# Master.net
KiCad netlist of a schematic drawn in Altium Designer
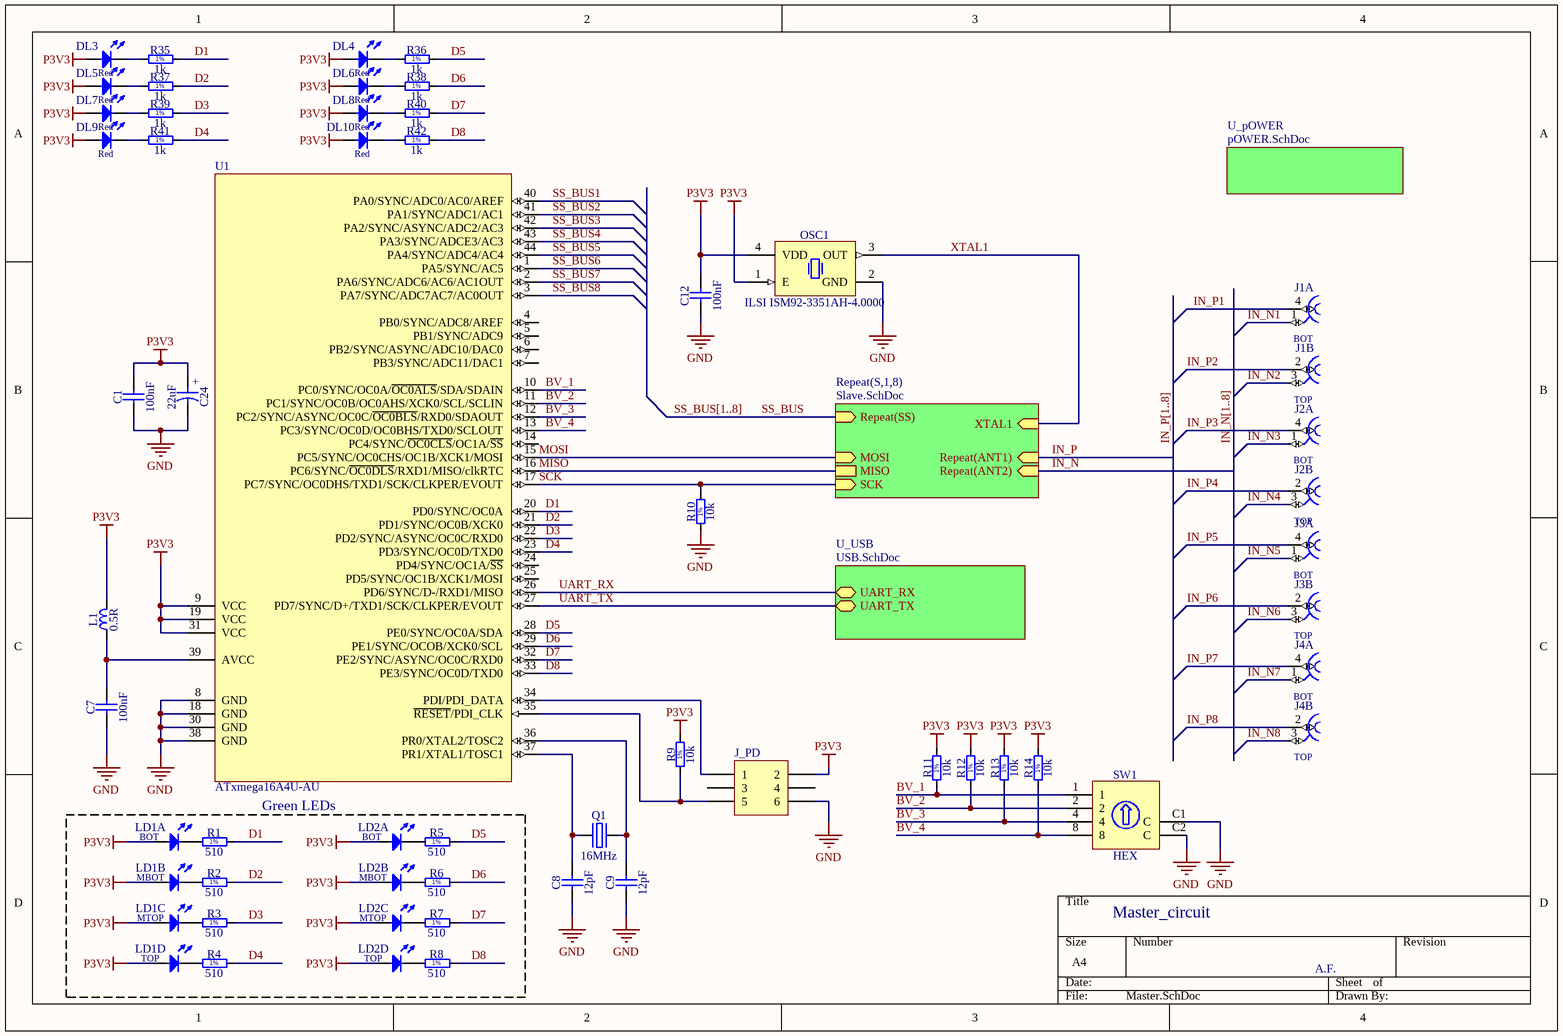
[diagram p0: Master.SchDoc]

(export (version "E")
  (design (tool "Eeschema 10.0.6"))
  (components
    (comp (ref "C1")
      (value "100nF")
      (footprint "CAPC1608X87N")
      (description "Non-polarised capacitor")
      (fields
        (field (name "PART NUMBER") "CC0603_100NF_50V_10%_X5R")
        (field (name "VOLTAGE") "50V")
        (field (name "AUTHOR") "CERN DEM MR")
      )
      (libsource (lib "Capacitors") (part "Capacitor - non polarized"))
    )
    (comp (ref "C7")
      (value "100nF")
      (footprint "CAPC1608X87N")
      (description "Non-polarised capacitor")
      (fields
        (field (name "PART NUMBER") "CC0603_100NF_50V_10%_X5R")
        (field (name "VOLTAGE") "50V")
        (field (name "AUTHOR") "CERN DEM MR")
      )
      (libsource (lib "Capacitors") (part "Capacitor - non polarized"))
    )
    (comp (ref "C8")
      (value "12pF")
      (footprint "CAPC1608X87N")
      (description "Non-polarised capacitor")
      (fields
        (field (name "PART NUMBER") "CC0603_12PF_50V_5%_NP0")
        (field (name "VOLTAGE") "50V")
        (field (name "AUTHOR") "CERN DEM JLC")
      )
      (libsource (lib "Capacitors") (part "Capacitor - non polarized"))
    )
    (comp (ref "C9")
      (value "12pF")
      (footprint "CAPC1608X87N")
      (description "Non-polarised capacitor")
      (fields
        (field (name "PART NUMBER") "CC0603_12PF_50V_5%_NP0")
        (field (name "VOLTAGE") "50V")
        (field (name "AUTHOR") "CERN DEM JLC")
      )
      (libsource (lib "Capacitors") (part "Capacitor - non polarized"))
    )
    (comp (ref "C12")
      (value "100nF")
      (footprint "CAPC1608X87N")
      (description "Non-polarised capacitor")
      (fields
        (field (name "PART NUMBER") "CC0603_100NF_50V_10%_X5R")
        (field (name "VOLTAGE") "50V")
        (field (name "AUTHOR") "CERN DEM MR")
      )
      (libsource (lib "Capacitors") (part "Capacitor - non polarized"))
    )
    (comp (ref "C24")
      (value "22uF")
      (footprint "CAPAE430X540N")
      (description "Polarised capacitor")
      (fields
        (field (name "PART NUMBER") "CAE430-540_22UF_10V_20%")
        (field (name "VOLTAGE") "10V")
        (field (name "AUTHOR") "CERN DEM JLC")
      )
      (libsource (lib "Capacitors") (part "Capacitor - polarized"))
    )
    (comp (ref "DL3")
      (value "Red")
      (footprint "LED_OSRAM_LSR976")
      (description "LED Red 1C 2A")
      (fields
        (field (name "PART NUMBER") "LED_OSRAM_LSR976")
        (field (name "MANUFACTURER") "OSRAM")
        (field (name "AUTHOR") "CERN DEM JLC")
      )
      (libsource (lib "ICs And Semiconductors") (part "LED Red 1C 2A"))
    )
    (comp (ref "DL4")
      (value "Red")
      (footprint "LED_OSRAM_LSR976")
      (description "LED Red 1C 2A")
      (fields
        (field (name "PART NUMBER") "LED_OSRAM_LSR976")
        (field (name "MANUFACTURER") "OSRAM")
        (field (name "AUTHOR") "CERN DEM JLC")
      )
      (libsource (lib "ICs And Semiconductors") (part "LED Red 1C 2A"))
    )
    (comp (ref "DL5")
      (value "Red")
      (footprint "LED_OSRAM_LSR976")
      (description "LED Red 1C 2A")
      (fields
        (field (name "PART NUMBER") "LED_OSRAM_LSR976")
        (field (name "MANUFACTURER") "OSRAM")
        (field (name "AUTHOR") "CERN DEM JLC")
      )
      (libsource (lib "ICs And Semiconductors") (part "LED Red 1C 2A"))
    )
    (comp (ref "DL6")
      (value "Red")
      (footprint "LED_OSRAM_LSR976")
      (description "LED Red 1C 2A")
      (fields
        (field (name "PART NUMBER") "LED_OSRAM_LSR976")
        (field (name "MANUFACTURER") "OSRAM")
        (field (name "AUTHOR") "CERN DEM JLC")
      )
      (libsource (lib "ICs And Semiconductors") (part "LED Red 1C 2A"))
    )
    (comp (ref "DL7")
      (value "Red")
      (footprint "LED_OSRAM_LSR976")
      (description "LED Red 1C 2A")
      (fields
        (field (name "PART NUMBER") "LED_OSRAM_LSR976")
        (field (name "MANUFACTURER") "OSRAM")
        (field (name "AUTHOR") "CERN DEM JLC")
      )
      (libsource (lib "ICs And Semiconductors") (part "LED Red 1C 2A"))
    )
    (comp (ref "DL8")
      (value "Red")
      (footprint "LED_OSRAM_LSR976")
      (description "LED Red 1C 2A")
      (fields
        (field (name "PART NUMBER") "LED_OSRAM_LSR976")
        (field (name "MANUFACTURER") "OSRAM")
        (field (name "AUTHOR") "CERN DEM JLC")
      )
      (libsource (lib "ICs And Semiconductors") (part "LED Red 1C 2A"))
    )
    (comp (ref "DL9")
      (value "Red")
      (footprint "LED_OSRAM_LSR976")
      (description "LED Red 1C 2A")
      (fields
        (field (name "PART NUMBER") "LED_OSRAM_LSR976")
        (field (name "MANUFACTURER") "OSRAM")
        (field (name "AUTHOR") "CERN DEM JLC")
      )
      (libsource (lib "ICs And Semiconductors") (part "LED Red 1C 2A"))
    )
    (comp (ref "DL10")
      (value "Red")
      (footprint "LED_OSRAM_LSR976")
      (description "LED Red 1C 2A")
      (fields
        (field (name "PART NUMBER") "LED_OSRAM_LSR976")
        (field (name "MANUFACTURER") "OSRAM")
        (field (name "AUTHOR") "CERN DEM JLC")
      )
      (libsource (lib "ICs And Semiconductors") (part "LED Red 1C 2A"))
    )
    (comp (ref "J1")
      (value "BNC")
      (footprint "RENHOTEC_RHT-610-0049")
      (description "Dual Right Angle 50 Ohm BNC Jack, White Valox Case")
      (fields
        (field (name "PART NUMBER") "RENHOTEC_RHT-610-0049")
        (field (name "MANUFACTURER") "RENHOTEC")
        (field (name "AUTHOR") "GK")
      )
      (libsource (lib "LIBRARY_SCH") (part "CON_BNC_DUAL"))
    )
    (comp (ref "J2")
      (value "Family")
      (footprint "RENHOTEC_RHT-610-0049")
      (description "Dual Right Angle 50 Ohm BNC Jack, White Valox Case")
      (fields
        (field (name "PART NUMBER") "RENHOTEC_RHT-610-0049")
        (field (name "MANUFACTURER") "RENHOTEC")
        (field (name "AUTHOR") "GK")
      )
      (libsource (lib "LIBRARY_SCH") (part "CON_BNC_DUAL"))
    )
    (comp (ref "J3")
      (value "Family")
      (footprint "RENHOTEC_RHT-610-0049")
      (description "Dual Right Angle 50 Ohm BNC Jack, White Valox Case")
      (fields
        (field (name "PART NUMBER") "RENHOTEC_RHT-610-0049")
        (field (name "MANUFACTURER") "RENHOTEC")
        (field (name "AUTHOR") "GK")
      )
      (libsource (lib "LIBRARY_SCH") (part "CON_BNC_DUAL"))
    )
    (comp (ref "J4")
      (value "Family")
      (footprint "RENHOTEC_RHT-610-0049")
      (description "Dual Right Angle 50 Ohm BNC Jack, White Valox Case")
      (fields
        (field (name "PART NUMBER") "RENHOTEC_RHT-610-0049")
        (field (name "MANUFACTURER") "RENHOTEC")
        (field (name "AUTHOR") "GK")
      )
      (libsource (lib "LIBRARY_SCH") (part "CON_BNC_DUAL"))
    )
    (comp (ref "J_PD")
      (value "~")
      (footprint "HDR2X3")
      (description "Header, 3-Pin, Dual row")
      (fields (field (name "PUBLISHER") "Altium Limited"))
      (libsource (lib "Miscellaneous Connectors") (part "Header 3X2"))
    )
    (comp (ref "L1")
      (value "0.5R")
      (footprint "Miscellaneous Devices:1608[0603]")
      (description "Ferrite Bead")
      (fields
        (field (name "POWER") "0.5A")
        (field (name "MANUFACTURER") "MURATA")
        (field (name "AUTHOR") "CERN DEM BC")
      )
      (libsource (lib "altium-import") (part "root_1_Inductor_"))
    )
    (comp (ref "LD1")
      (value "Green")
      (footprint "LED_BIVAR_H485CGDL")
      (description "LED x4 Green 1C2A-BOT_3C4A_5C6A_7C8A-TOP")
      (fields
        (field (name "PART NUMBER") "LED_BIVAR_H485CGDL")
        (field (name "MANUFACTURER") "BIVAR")
        (field (name "AUTHOR") "CERN DEM JLC")
      )
      (libsource (lib "RFID_system") (part "LED x4 Green 1C2A-BOT_3C4A_5C6A_7C8A-TOP"))
    )
    (comp (ref "LD2")
      (value "Green")
      (footprint "LED_BIVAR_H485CGDL")
      (description "LED x4 Green 1C2A-BOT_3C4A_5C6A_7C8A-TOP")
      (fields
        (field (name "PART NUMBER") "LED_BIVAR_H485CGDL")
        (field (name "MANUFACTURER") "BIVAR")
        (field (name "AUTHOR") "CERN DEM JLC")
      )
      (libsource (lib "RFID_system") (part "LED x4 Green 1C2A-BOT_3C4A_5C6A_7C8A-TOP"))
    )
    (comp (ref "OSC1")
      (value "ILSI ISM92-3351AH-4.0000")
      (footprint "OSCSC250P320X500X130-4N")
      (description "Oscillator 4 pins 3.3V 4MHz")
      (libsource (lib "Crystals & Oscillators") (part "Oscillator 1E 2GND 3OUT 4VDD"))
    )
    (comp (ref "Q1")
      (value "16MHz")
      (footprint "XTAL1160X490X430")
      (description "Quartz Crystal")
      (fields
        (field (name "PART NUMBER") "XTAL_16MHZ_IQD_LFXTAL003237")
        (field (name "MANUFACTURER") "IQD FREQUENCY PRODUCTS")
        (field (name "AUTHOR") "CERN DEM MR")
      )
      (libsource (lib "ICs And Semiconductors") (part "Quartz Crystal"))
    )
    (comp (ref "R1")
      (value "510")
      (footprint "RESC1608X55N")
      (description "Resistor - 1%")
      (fields
        (field (name "PART NUMBER") "R0603_510R_1%_0.1W_100PPM")
        (field (name "POWER") "0.1W")
        (field (name "AUTHOR") "CERN DEM JLC")
      )
      (libsource (lib "Resistors") (part "Resistor - 1%"))
    )
    (comp (ref "R2")
      (value "510")
      (footprint "RESC1608X55N")
      (description "Resistor - 1%")
      (fields
        (field (name "PART NUMBER") "R0603_510R_1%_0.1W_100PPM")
        (field (name "POWER") "0.1W")
        (field (name "AUTHOR") "CERN DEM JLC")
      )
      (libsource (lib "Resistors") (part "Resistor - 1%"))
    )
    (comp (ref "R3")
      (value "510")
      (footprint "RESC1608X55N")
      (description "Resistor - 1%")
      (fields
        (field (name "PART NUMBER") "R0603_510R_1%_0.1W_100PPM")
        (field (name "POWER") "0.1W")
        (field (name "AUTHOR") "CERN DEM JLC")
      )
      (libsource (lib "Resistors") (part "Resistor - 1%"))
    )
    (comp (ref "R4")
      (value "510")
      (footprint "RESC1608X55N")
      (description "Resistor - 1%")
      (fields
        (field (name "PART NUMBER") "R0603_510R_1%_0.1W_100PPM")
        (field (name "POWER") "0.1W")
        (field (name "AUTHOR") "CERN DEM JLC")
      )
      (libsource (lib "Resistors") (part "Resistor - 1%"))
    )
    (comp (ref "R5")
      (value "510")
      (footprint "RESC1608X55N")
      (description "Resistor - 1%")
      (fields
        (field (name "PART NUMBER") "R0603_510R_1%_0.1W_100PPM")
        (field (name "POWER") "0.1W")
        (field (name "AUTHOR") "CERN DEM JLC")
      )
      (libsource (lib "Resistors") (part "Resistor - 1%"))
    )
    (comp (ref "R6")
      (value "510")
      (footprint "RESC1608X55N")
      (description "Resistor - 1%")
      (fields
        (field (name "PART NUMBER") "R0603_510R_1%_0.1W_100PPM")
        (field (name "POWER") "0.1W")
        (field (name "AUTHOR") "CERN DEM JLC")
      )
      (libsource (lib "Resistors") (part "Resistor - 1%"))
    )
    (comp (ref "R7")
      (value "510")
      (footprint "RESC1608X55N")
      (description "Resistor - 1%")
      (fields
        (field (name "PART NUMBER") "R0603_510R_1%_0.1W_100PPM")
        (field (name "POWER") "0.1W")
        (field (name "AUTHOR") "CERN DEM JLC")
      )
      (libsource (lib "Resistors") (part "Resistor - 1%"))
    )
    (comp (ref "R8")
      (value "510")
      (footprint "RESC1608X55N")
      (description "Resistor - 1%")
      (fields
        (field (name "PART NUMBER") "R0603_510R_1%_0.1W_100PPM")
        (field (name "POWER") "0.1W")
        (field (name "AUTHOR") "CERN DEM JLC")
      )
      (libsource (lib "Resistors") (part "Resistor - 1%"))
    )
    (comp (ref "R9")
      (value "10k")
      (footprint "RESC1608X55N")
      (description "Resistor - 1%")
      (fields
        (field (name "PART NUMBER") "R0603_10K_1%_0.1W_100PPM")
        (field (name "POWER") "0.1W")
        (field (name "AUTHOR") "CERN DEM JLC")
      )
      (libsource (lib "Resistors") (part "Resistor - 1%"))
    )
    (comp (ref "R10")
      (value "10k")
      (footprint "RESC1608X55N")
      (description "Resistor - 1%")
      (fields
        (field (name "PART NUMBER") "R0603_10K_1%_0.1W_100PPM")
        (field (name "POWER") "0.1W")
        (field (name "AUTHOR") "CERN DEM JLC")
      )
      (libsource (lib "Resistors") (part "Resistor - 1%"))
    )
    (comp (ref "R11")
      (value "10k")
      (footprint "RESC1608X55N")
      (description "Resistor - 1%")
      (fields
        (field (name "PART NUMBER") "R0603_10K_1%_0.1W_100PPM")
        (field (name "POWER") "0.1W")
        (field (name "AUTHOR") "CERN DEM JLC")
      )
      (libsource (lib "Resistors") (part "Resistor - 1%"))
    )
    (comp (ref "R12")
      (value "10k")
      (footprint "RESC1608X55N")
      (description "Resistor - 1%")
      (fields
        (field (name "PART NUMBER") "R0603_10K_1%_0.1W_100PPM")
        (field (name "POWER") "0.1W")
        (field (name "AUTHOR") "CERN DEM JLC")
      )
      (libsource (lib "Resistors") (part "Resistor - 1%"))
    )
    (comp (ref "R13")
      (value "10k")
      (footprint "RESC1608X55N")
      (description "Resistor - 1%")
      (fields
        (field (name "PART NUMBER") "R0603_10K_1%_0.1W_100PPM")
        (field (name "POWER") "0.1W")
        (field (name "AUTHOR") "CERN DEM JLC")
      )
      (libsource (lib "Resistors") (part "Resistor - 1%"))
    )
    (comp (ref "R14")
      (value "10k")
      (footprint "RESC1608X55N")
      (description "Resistor - 1%")
      (fields
        (field (name "PART NUMBER") "R0603_10K_1%_0.1W_100PPM")
        (field (name "POWER") "0.1W")
        (field (name "AUTHOR") "CERN DEM JLC")
      )
      (libsource (lib "Resistors") (part "Resistor - 1%"))
    )
    (comp (ref "R35")
      (value "1k")
      (footprint "RESC1608X50N")
      (description "Resistor - 1%")
      (fields
        (field (name "PART NUMBER") "R0805_1K_1%_0.33W_100PPM_VISHAY_CRCW-HP")
        (field (name "POWER") "0.33W")
        (field (name "AUTHOR") "CERN DEM JLC")
      )
      (libsource (lib "Resistors") (part "Resistor - 1%"))
    )
    (comp (ref "R36")
      (value "1k")
      (footprint "RESC1608X50N")
      (description "Resistor - 1%")
      (fields
        (field (name "PART NUMBER") "R0805_1K_1%_0.33W_100PPM_VISHAY_CRCW-HP")
        (field (name "POWER") "0.33W")
        (field (name "AUTHOR") "CERN DEM JLC")
      )
      (libsource (lib "Resistors") (part "Resistor - 1%"))
    )
    (comp (ref "R37")
      (value "1k")
      (footprint "RESC1608X50N")
      (description "Resistor - 1%")
      (fields
        (field (name "PART NUMBER") "R0805_1K_1%_0.33W_100PPM_VISHAY_CRCW-HP")
        (field (name "POWER") "0.33W")
        (field (name "AUTHOR") "CERN DEM JLC")
      )
      (libsource (lib "Resistors") (part "Resistor - 1%"))
    )
    (comp (ref "R38")
      (value "1k")
      (footprint "RESC1608X50N")
      (description "Resistor - 1%")
      (fields
        (field (name "PART NUMBER") "R0805_1K_1%_0.33W_100PPM_VISHAY_CRCW-HP")
        (field (name "POWER") "0.33W")
        (field (name "AUTHOR") "CERN DEM JLC")
      )
      (libsource (lib "Resistors") (part "Resistor - 1%"))
    )
    (comp (ref "R39")
      (value "1k")
      (footprint "RESC1608X50N")
      (description "Resistor - 1%")
      (fields
        (field (name "PART NUMBER") "R0805_1K_1%_0.33W_100PPM_VISHAY_CRCW-HP")
        (field (name "POWER") "0.33W")
        (field (name "AUTHOR") "CERN DEM JLC")
      )
      (libsource (lib "Resistors") (part "Resistor - 1%"))
    )
    (comp (ref "R40")
      (value "1k")
      (footprint "RESC1608X50N")
      (description "Resistor - 1%")
      (fields
        (field (name "PART NUMBER") "R0805_1K_1%_0.33W_100PPM_VISHAY_CRCW-HP")
        (field (name "POWER") "0.33W")
        (field (name "AUTHOR") "CERN DEM JLC")
      )
      (libsource (lib "Resistors") (part "Resistor - 1%"))
    )
    (comp (ref "R41")
      (value "1k")
      (footprint "RESC1608X50N")
      (description "Resistor - 1%")
      (fields
        (field (name "PART NUMBER") "R0805_1K_1%_0.33W_100PPM_VISHAY_CRCW-HP")
        (field (name "POWER") "0.33W")
        (field (name "AUTHOR") "CERN DEM JLC")
      )
      (libsource (lib "Resistors") (part "Resistor - 1%"))
    )
    (comp (ref "R42")
      (value "1k")
      (footprint "RESC1608X50N")
      (description "Resistor - 1%")
      (fields
        (field (name "PART NUMBER") "R0805_1K_1%_0.33W_100PPM_VISHAY_CRCW-HP")
        (field (name "POWER") "0.33W")
        (field (name "AUTHOR") "CERN DEM JLC")
      )
      (libsource (lib "Resistors") (part "Resistor - 1%"))
    )
    (comp (ref "SW1")
      (value "HEX")
      (footprint "SW_OMRON_A6RV-162RF")
      (description "Rotary Code Switch 1 2 4 8 C1 C2")
      (fields
        (field (name "PART NUMBER") "SW_OMRON_A6RV-162RF or ERD716RR")
        (field (name "MANUFACTURER") "OMRON")
        (field (name "AUTHOR") "CERN DEM JLC")
      )
      (libsource (lib "Eletro-mechanical") (part "SW Rotary 1 2 4 8 C1 C2"))
    )
    (comp (ref "U1")
      (value "ATxmega16A4U-AU")
      (footprint "44A_N")
      (fields (field (name "PUBLISHER") "Altium Limited"))
      (libsource (lib "RFID_system_atxmegau") (part "ATxmega16A4-AU"))
    )
  )
  (nets
    (net (code "2") (name "/BV_1") (class "Default")
      (node (ref "R11") (pin "1") (pinfunction "1_1") (pintype "passive"))
      (node (ref "SW1") (pin "1") (pinfunction "1_1") (pintype "passive"))
      (node (ref "U1") (pin "10") (pinfunction "PC0/SYNC/OC0A/~{OC0ALS}/SDA/SDAIN_10") (pintype "bidirectional"))
    )
    (net (code "3") (name "/BV_2") (class "Default")
      (node (ref "R12") (pin "1") (pinfunction "1_1") (pintype "passive"))
      (node (ref "SW1") (pin "2") (pinfunction "2_2") (pintype "passive"))
      (node (ref "U1") (pin "11") (pinfunction "PC1/SYNC/OC0B/OC0AHS/XCK0/SCL/SCLIN_11") (pintype "bidirectional"))
    )
    (net (code "4") (name "/BV_3") (class "Default")
      (node (ref "R13") (pin "1") (pinfunction "1_1") (pintype "passive"))
      (node (ref "SW1") (pin "4") (pinfunction "4_4") (pintype "passive"))
      (node (ref "U1") (pin "12") (pinfunction "PC2/SYNC/ASYNC/OC0C/~{OC0BLS}/RXD0/SDAOUT_12") (pintype "bidirectional"))
    )
    (net (code "5") (name "/BV_4") (class "Default")
      (node (ref "R14") (pin "1") (pinfunction "1_1") (pintype "passive"))
      (node (ref "SW1") (pin "8") (pinfunction "8_8") (pintype "passive"))
      (node (ref "U1") (pin "13") (pinfunction "PC3/SYNC/OC0D/OC0BHS/TXD0/SCLOUT_13") (pintype "bidirectional"))
    )
    (net (code "6") (name "/D1") (class "Default")
      (node (ref "R1") (pin "2") (pinfunction "2_2") (pintype "passive"))
      (node (ref "R35") (pin "1") (pinfunction "1_1") (pintype "passive"))
      (node (ref "U1") (pin "20") (pinfunction "PD0/SYNC/OC0A_20") (pintype "bidirectional"))
    )
    (net (code "7") (name "/D2") (class "Default")
      (node (ref "R2") (pin "2") (pinfunction "2_2") (pintype "passive"))
      (node (ref "R37") (pin "1") (pinfunction "1_1") (pintype "passive"))
      (node (ref "U1") (pin "21") (pinfunction "PD1/SYNC/OC0B/XCK0_21") (pintype "bidirectional"))
    )
    (net (code "8") (name "/D3") (class "Default")
      (node (ref "R3") (pin "2") (pinfunction "2_2") (pintype "passive"))
      (node (ref "R39") (pin "1") (pinfunction "1_1") (pintype "passive"))
      (node (ref "U1") (pin "22") (pinfunction "PD2/SYNC/ASYNC/OC0C/RXD0_22") (pintype "bidirectional"))
    )
    (net (code "9") (name "/D4") (class "Default")
      (node (ref "R4") (pin "2") (pinfunction "2_2") (pintype "passive"))
      (node (ref "R41") (pin "1") (pinfunction "1_1") (pintype "passive"))
      (node (ref "U1") (pin "23") (pinfunction "PD3/SYNC/OC0D/TXD0_23") (pintype "bidirectional"))
    )
    (net (code "10") (name "/D5") (class "Default")
      (node (ref "R36") (pin "1") (pinfunction "1_1") (pintype "passive"))
      (node (ref "R5") (pin "2") (pinfunction "2_2") (pintype "passive"))
      (node (ref "U1") (pin "28") (pinfunction "PE0/SYNC/OC0A/SDA_28") (pintype "bidirectional"))
    )
    (net (code "11") (name "/D6") (class "Default")
      (node (ref "R38") (pin "1") (pinfunction "1_1") (pintype "passive"))
      (node (ref "R6") (pin "2") (pinfunction "2_2") (pintype "passive"))
      (node (ref "U1") (pin "29") (pinfunction "PE1/SYNC/OCOB/XCK0/SCL_29") (pintype "bidirectional"))
    )
    (net (code "12") (name "/D7") (class "Default")
      (node (ref "R40") (pin "1") (pinfunction "1_1") (pintype "passive"))
      (node (ref "R7") (pin "2") (pinfunction "2_2") (pintype "passive"))
      (node (ref "U1") (pin "32") (pinfunction "PE2/SYNC/ASYNC/OC0C/RXD0_32") (pintype "bidirectional"))
    )
    (net (code "13") (name "/D8") (class "Default")
      (node (ref "R42") (pin "1") (pinfunction "1_1") (pintype "passive"))
      (node (ref "R8") (pin "2") (pinfunction "2_2") (pintype "passive"))
      (node (ref "U1") (pin "33") (pinfunction "PE3/SYNC/OC0D/TXD0_33") (pintype "bidirectional"))
    )
    (net (code "15") (name "/IN_N1") (class "Default")
      (node (ref "J1") (pin "1") (pinfunction "1_1") (pintype "bidirectional"))
    )
    (net (code "16") (name "/IN_N2") (class "Default")
      (node (ref "J1") (pin "3") (pinfunction "3_3") (pintype "bidirectional"))
    )
    (net (code "17") (name "/IN_N3") (class "Default")
      (node (ref "J2") (pin "1") (pinfunction "1_1") (pintype "bidirectional"))
    )
    (net (code "18") (name "/IN_N4") (class "Default")
      (node (ref "J2") (pin "3") (pinfunction "3_3") (pintype "bidirectional"))
    )
    (net (code "19") (name "/IN_N5") (class "Default")
      (node (ref "J3") (pin "1") (pinfunction "1_1") (pintype "bidirectional"))
    )
    (net (code "20") (name "/IN_N6") (class "Default")
      (node (ref "J3") (pin "3") (pinfunction "3_3") (pintype "bidirectional"))
    )
    (net (code "21") (name "/IN_N7") (class "Default")
      (node (ref "J4") (pin "1") (pinfunction "1_1") (pintype "bidirectional"))
    )
    (net (code "22") (name "/IN_N8") (class "Default")
      (node (ref "J4") (pin "3") (pinfunction "3_3") (pintype "bidirectional"))
    )
    (net (code "25") (name "/IN_P1") (class "Default")
      (node (ref "J1") (pin "4") (pinfunction "4_4") (pintype "bidirectional"))
    )
    (net (code "26") (name "/IN_P2") (class "Default")
      (node (ref "J1") (pin "2") (pinfunction "2_2") (pintype "bidirectional"))
    )
    (net (code "27") (name "/IN_P3") (class "Default")
      (node (ref "J2") (pin "4") (pinfunction "4_4") (pintype "bidirectional"))
    )
    (net (code "28") (name "/IN_P4") (class "Default")
      (node (ref "J2") (pin "2") (pinfunction "2_2") (pintype "bidirectional"))
    )
    (net (code "29") (name "/IN_P5") (class "Default")
      (node (ref "J3") (pin "4") (pinfunction "4_4") (pintype "bidirectional"))
    )
    (net (code "30") (name "/IN_P6") (class "Default")
      (node (ref "J3") (pin "2") (pinfunction "2_2") (pintype "bidirectional"))
    )
    (net (code "31") (name "/IN_P7") (class "Default")
      (node (ref "J4") (pin "4") (pinfunction "4_4") (pintype "bidirectional"))
    )
    (net (code "32") (name "/IN_P8") (class "Default")
      (node (ref "J4") (pin "2") (pinfunction "2_2") (pintype "bidirectional"))
    )
    (net (code "34") (name "/MISO") (class "Default")
      (node (ref "U1") (pin "16") (pinfunction "PC6/SYNC/~{OC0DLS}/RXD1/MISO/clkRTC_16") (pintype "bidirectional"))
    )
    (net (code "35") (name "/MOSI") (class "Default")
      (node (ref "U1") (pin "15") (pinfunction "PC5/SYNC/OC0CHS/OC1B/XCK1/MOSI_15") (pintype "bidirectional"))
    )
    (net (code "36") (name "/SCK") (class "Default")
      (node (ref "R10") (pin "2") (pinfunction "2_2") (pintype "passive"))
      (node (ref "U1") (pin "17") (pinfunction "PC7/SYNC/OC0DHS/TXD1/SCK/CLKPER/EVOUT_17") (pintype "bidirectional"))
    )
    (net (code "38") (name "/SS_BUS1") (class "Default")
      (node (ref "U1") (pin "40") (pinfunction "PA0/SYNC/ADC0/AC0/AREF_40") (pintype "bidirectional"))
    )
    (net (code "39") (name "/SS_BUS2") (class "Default")
      (node (ref "U1") (pin "41") (pinfunction "PA1/SYNC/ADC1/AC1_41") (pintype "bidirectional"))
    )
    (net (code "40") (name "/SS_BUS3") (class "Default")
      (node (ref "U1") (pin "42") (pinfunction "PA2/SYNC/ASYNC/ADC2/AC3_42") (pintype "bidirectional"))
    )
    (net (code "41") (name "/SS_BUS4") (class "Default")
      (node (ref "U1") (pin "43") (pinfunction "PA3/SYNC/ADCE3/AC3_43") (pintype "bidirectional"))
    )
    (net (code "42") (name "/SS_BUS5") (class "Default")
      (node (ref "U1") (pin "44") (pinfunction "PA4/SYNC/ADC4/AC4_44") (pintype "bidirectional"))
    )
    (net (code "43") (name "/SS_BUS6") (class "Default")
      (node (ref "U1") (pin "1") (pinfunction "PA5/SYNC/AC5_1") (pintype "bidirectional"))
    )
    (net (code "44") (name "/SS_BUS7") (class "Default")
      (node (ref "U1") (pin "2") (pinfunction "PA6/SYNC/ADC6/AC6/AC1OUT_2") (pintype "bidirectional"))
    )
    (net (code "45") (name "/SS_BUS8") (class "Default")
      (node (ref "U1") (pin "3") (pinfunction "PA7/SYNC/ADC7AC7/AC0OUT_3") (pintype "bidirectional"))
    )
    (net (code "47") (name "/UART_RX") (class "Default")
      (node (ref "U1") (pin "26") (pinfunction "PD6/SYNC/D-/RXD1/MISO_26") (pintype "bidirectional"))
    )
    (net (code "48") (name "/UART_TX") (class "Default")
      (node (ref "U1") (pin "27") (pinfunction "PD7/SYNC/D+/TXD1/SCK/CLKPER/EVOUT_27") (pintype "bidirectional"))
    )
    (net (code "49") (name "/XTAL1") (class "Default")
      (node (ref "OSC1") (pin "3") (pinfunction "OUT_3") (pintype "output"))
    )
    (net (code "50") (name "GND") (class "Default")
      (node (ref "C1") (pin "1") (pinfunction "1_1") (pintype "passive"))
      (node (ref "C12") (pin "1") (pinfunction "1_1") (pintype "passive"))
      (node (ref "C24") (pin "2") (pinfunction "2_2") (pintype "passive"))
      (node (ref "C7") (pin "1") (pinfunction "1_1") (pintype "passive"))
      (node (ref "C8") (pin "1") (pinfunction "1_1") (pintype "passive"))
      (node (ref "C9") (pin "1") (pinfunction "1_1") (pintype "passive"))
      (node (ref "J_PD") (pin "6") (pinfunction "6_6") (pintype "passive"))
      (node (ref "OSC1") (pin "2") (pinfunction "GND_2") (pintype "power_in"))
      (node (ref "R10") (pin "1") (pinfunction "1_1") (pintype "passive"))
      (node (ref "SW1") (pin "C1") (pinfunction "C_C1") (pintype "passive"))
      (node (ref "SW1") (pin "C2") (pinfunction "C_C2") (pintype "passive"))
      (node (ref "U1") (pin "18") (pinfunction "GND_18") (pintype "power_in"))
      (node (ref "U1") (pin "30") (pinfunction "GND_30") (pintype "power_in"))
      (node (ref "U1") (pin "38") (pinfunction "GND_38") (pintype "power_in"))
      (node (ref "U1") (pin "8") (pinfunction "GND_8") (pintype "power_in"))
    )
    (net (code "51") (name "Net-(DL3-C)") (class "Default")
      (node (ref "DL3") (pin "1") (pinfunction "C_1") (pintype "passive"))
      (node (ref "R35") (pin "2") (pinfunction "2_2") (pintype "passive"))
    )
    (net (code "52") (name "Net-(DL4-C)") (class "Default")
      (node (ref "DL4") (pin "1") (pinfunction "C_1") (pintype "passive"))
      (node (ref "R36") (pin "2") (pinfunction "2_2") (pintype "passive"))
    )
    (net (code "53") (name "Net-(DL5-C)") (class "Default")
      (node (ref "DL5") (pin "1") (pinfunction "C_1") (pintype "passive"))
      (node (ref "R37") (pin "2") (pinfunction "2_2") (pintype "passive"))
    )
    (net (code "54") (name "Net-(DL6-C)") (class "Default")
      (node (ref "DL6") (pin "1") (pinfunction "C_1") (pintype "passive"))
      (node (ref "R38") (pin "2") (pinfunction "2_2") (pintype "passive"))
    )
    (net (code "55") (name "Net-(DL7-C)") (class "Default")
      (node (ref "DL7") (pin "1") (pinfunction "C_1") (pintype "passive"))
      (node (ref "R39") (pin "2") (pinfunction "2_2") (pintype "passive"))
    )
    (net (code "56") (name "Net-(DL8-C)") (class "Default")
      (node (ref "DL8") (pin "1") (pinfunction "C_1") (pintype "passive"))
      (node (ref "R40") (pin "2") (pinfunction "2_2") (pintype "passive"))
    )
    (net (code "57") (name "Net-(DL9-C)") (class "Default")
      (node (ref "DL9") (pin "1") (pinfunction "C_1") (pintype "passive"))
      (node (ref "R41") (pin "2") (pinfunction "2_2") (pintype "passive"))
    )
    (net (code "58") (name "Net-(DL10-C)") (class "Default")
      (node (ref "DL10") (pin "1") (pinfunction "C_1") (pintype "passive"))
      (node (ref "R42") (pin "2") (pinfunction "2_2") (pintype "passive"))
    )
    (net (code "59") (name "Net-(LD1A-C)") (class "Default")
      (node (ref "LD1") (pin "1") (pinfunction "C_1") (pintype "passive"))
      (node (ref "R1") (pin "1") (pinfunction "1_1") (pintype "passive"))
    )
    (net (code "60") (name "Net-(LD1B-C)") (class "Default")
      (node (ref "LD1") (pin "3") (pinfunction "C_3") (pintype "passive"))
      (node (ref "R2") (pin "1") (pinfunction "1_1") (pintype "passive"))
    )
    (net (code "61") (name "Net-(LD1C-C)") (class "Default")
      (node (ref "LD1") (pin "5") (pinfunction "C_5") (pintype "passive"))
      (node (ref "R3") (pin "1") (pinfunction "1_1") (pintype "passive"))
    )
    (net (code "62") (name "Net-(LD1D-C)") (class "Default")
      (node (ref "LD1") (pin "7") (pinfunction "C_7") (pintype "passive"))
      (node (ref "R4") (pin "1") (pinfunction "1_1") (pintype "passive"))
    )
    (net (code "63") (name "Net-(LD2A-C)") (class "Default")
      (node (ref "LD2") (pin "1") (pinfunction "C_1") (pintype "passive"))
      (node (ref "R5") (pin "1") (pinfunction "1_1") (pintype "passive"))
    )
    (net (code "64") (name "Net-(LD2B-C)") (class "Default")
      (node (ref "LD2") (pin "3") (pinfunction "C_3") (pintype "passive"))
      (node (ref "R6") (pin "1") (pinfunction "1_1") (pintype "passive"))
    )
    (net (code "65") (name "Net-(LD2C-C)") (class "Default")
      (node (ref "LD2") (pin "5") (pinfunction "C_5") (pintype "passive"))
      (node (ref "R7") (pin "1") (pinfunction "1_1") (pintype "passive"))
    )
    (net (code "66") (name "Net-(LD2D-C)") (class "Default")
      (node (ref "LD2") (pin "7") (pinfunction "C_7") (pintype "passive"))
      (node (ref "R8") (pin "1") (pinfunction "1_1") (pintype "passive"))
    )
    (net (code "67") (name "Net-(Q1-OSC1)") (class "Default")
      (node (ref "C8") (pin "2") (pinfunction "2_2") (pintype "passive"))
      (node (ref "Q1") (pin "1") (pinfunction "OSC1_1") (pintype "passive"))
      (node (ref "U1") (pin "37") (pinfunction "PR1/XTAL1/TOSC1_37") (pintype "bidirectional"))
    )
    (net (code "68") (name "Net-(Q1-OSC2)") (class "Default")
      (node (ref "C9") (pin "2") (pinfunction "2_2") (pintype "passive"))
      (node (ref "Q1") (pin "2") (pinfunction "OSC2_2") (pintype "passive"))
      (node (ref "U1") (pin "36") (pinfunction "PR0/XTAL2/TOSC2_36") (pintype "bidirectional"))
    )
    (net (code "69") (name "Net-(U1-AVCC)") (class "Default")
      (node (ref "C7") (pin "2") (pinfunction "2_2") (pintype "passive"))
      (node (ref "L1") (pin "1") (pinfunction "1_1") (pintype "passive"))
      (node (ref "U1") (pin "39") (pinfunction "AVCC_39") (pintype "power_in"))
    )
    (net (code "70") (name "Net-(U1-PDI{slash}PDI_DATA)") (class "Default")
      (node (ref "J_PD") (pin "1") (pinfunction "1_1") (pintype "passive"))
      (node (ref "U1") (pin "34") (pinfunction "PDI/PDI_DATA_34") (pintype "bidirectional"))
    )
    (net (code "71") (name "Net-(U1-~{RESET}{slash}PDI_CLK)") (class "Default")
      (node (ref "J_PD") (pin "5") (pinfunction "5_5") (pintype "passive"))
      (node (ref "R9") (pin "1") (pinfunction "1_1") (pintype "passive"))
      (node (ref "U1") (pin "35") (pinfunction "~{RESET}/PDI_CLK_35") (pintype "input"))
    )
    (net (code "72") (name "P3V3") (class "Default")
      (node (ref "C1") (pin "2") (pinfunction "2_2") (pintype "passive"))
      (node (ref "C12") (pin "2") (pinfunction "2_2") (pintype "passive"))
      (node (ref "C24") (pin "1") (pinfunction "1_1") (pintype "passive"))
      (node (ref "DL10") (pin "2") (pinfunction "A_2") (pintype "passive"))
      (node (ref "DL3") (pin "2") (pinfunction "A_2") (pintype "passive"))
      (node (ref "DL4") (pin "2") (pinfunction "A_2") (pintype "passive"))
      (node (ref "DL5") (pin "2") (pinfunction "A_2") (pintype "passive"))
      (node (ref "DL6") (pin "2") (pinfunction "A_2") (pintype "passive"))
      (node (ref "DL7") (pin "2") (pinfunction "A_2") (pintype "passive"))
      (node (ref "DL8") (pin "2") (pinfunction "A_2") (pintype "passive"))
      (node (ref "DL9") (pin "2") (pinfunction "A_2") (pintype "passive"))
      (node (ref "J_PD") (pin "2") (pinfunction "2_2") (pintype "passive"))
      (node (ref "L1") (pin "2") (pinfunction "2_2") (pintype "passive"))
      (node (ref "LD1") (pin "2") (pinfunction "A_2") (pintype "passive"))
      (node (ref "LD1") (pin "4") (pinfunction "A_4") (pintype "passive"))
      (node (ref "LD1") (pin "6") (pinfunction "A_6") (pintype "passive"))
      (node (ref "LD1") (pin "8") (pinfunction "A_8") (pintype "passive"))
      (node (ref "LD2") (pin "2") (pinfunction "A_2") (pintype "passive"))
      (node (ref "LD2") (pin "4") (pinfunction "A_4") (pintype "passive"))
      (node (ref "LD2") (pin "6") (pinfunction "A_6") (pintype "passive"))
      (node (ref "LD2") (pin "8") (pinfunction "A_8") (pintype "passive"))
      (node (ref "OSC1") (pin "1") (pinfunction "E_1") (pintype "input"))
      (node (ref "OSC1") (pin "4") (pinfunction "VDD_4") (pintype "power_in"))
      (node (ref "R11") (pin "2") (pinfunction "2_2") (pintype "passive"))
      (node (ref "R12") (pin "2") (pinfunction "2_2") (pintype "passive"))
      (node (ref "R13") (pin "2") (pinfunction "2_2") (pintype "passive"))
      (node (ref "R14") (pin "2") (pinfunction "2_2") (pintype "passive"))
      (node (ref "R9") (pin "2") (pinfunction "2_2") (pintype "passive"))
      (node (ref "U1") (pin "19") (pinfunction "VCC_19") (pintype "power_in"))
      (node (ref "U1") (pin "31") (pinfunction "VCC_31") (pintype "power_in"))
      (node (ref "U1") (pin "9") (pinfunction "VCC_9") (pintype "power_in"))
    )
    (net (code "73") (name "unconnected-(J_PD-Pad3)") (class "Default")
      (node (ref "J_PD") (pin "3") (pinfunction "3_3") (pintype "passive"))
    )
    (net (code "74") (name "unconnected-(J_PD-Pad4)") (class "Default")
      (node (ref "J_PD") (pin "4") (pinfunction "4_4") (pintype "passive"))
    )
    (net (code "75") (name "unconnected-(U1-PB0{slash}SYNC{slash}ADC8{slash}AREF-Pad4)") (class "Default")
      (node (ref "U1") (pin "4") (pinfunction "PB0/SYNC/ADC8/AREF_4") (pintype "bidirectional"))
    )
    (net (code "76") (name "unconnected-(U1-PB1{slash}SYNC{slash}ADC9-Pad5)") (class "Default")
      (node (ref "U1") (pin "5") (pinfunction "PB1/SYNC/ADC9_5") (pintype "bidirectional"))
    )
    (net (code "77") (name "unconnected-(U1-PB2{slash}SYNC{slash}ASYNC{slash}ADC10{slash}DAC0-Pad6)") (class "Default")
      (node (ref "U1") (pin "6") (pinfunction "PB2/SYNC/ASYNC/ADC10/DAC0_6") (pintype "bidirectional"))
    )
    (net (code "78") (name "unconnected-(U1-PB3{slash}SYNC{slash}ADC11{slash}DAC1-Pad7)") (class "Default")
      (node (ref "U1") (pin "7") (pinfunction "PB3/SYNC/ADC11/DAC1_7") (pintype "bidirectional"))
    )
    (net (code "79") (name "unconnected-(U1-PC4{slash}SYNC{slash}~{OC0CLS}{slash}OC1A{slash}~{SS}-Pad14)") (class "Default")
      (node (ref "U1") (pin "14") (pinfunction "PC4/SYNC/~{OC0CLS}/OC1A/~{SS}_14") (pintype "bidirectional"))
    )
    (net (code "80") (name "unconnected-(U1-PD4{slash}SYNC{slash}OC1A{slash}~{SS}-Pad24)") (class "Default")
      (node (ref "U1") (pin "24") (pinfunction "PD4/SYNC/OC1A/~{SS}_24") (pintype "bidirectional"))
    )
    (net (code "81") (name "unconnected-(U1-PD5{slash}SYNC{slash}OC1B{slash}XCK1{slash}MOSI-Pad25)") (class "Default")
      (node (ref "U1") (pin "25") (pinfunction "PD5/SYNC/OC1B/XCK1/MOSI_25") (pintype "bidirectional"))
    )
  )
)
